# Snake_Game.net
KiCad netlist of a schematic drawn in EAGLE
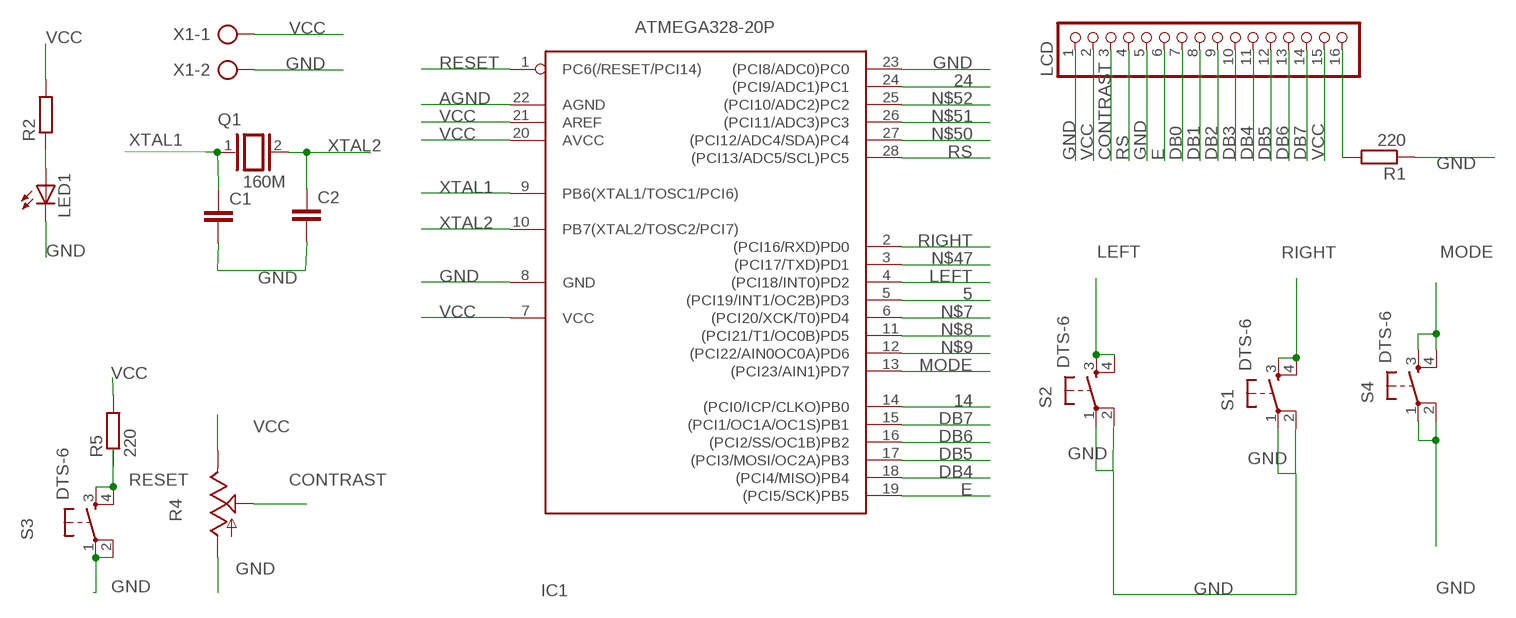
[diagram p0: schematic, sheet 1]

(export (version "E")
  (design (tool "Eeschema 10.0.6"))
  (components
    (comp (ref "C1")
      (value "C2.5/2")
      (footprint "eagle-import:C2.5-2")
      (libsource (lib "eagle-import") (part "C2.5/2"))
    )
    (comp (ref "C2")
      (value "C2.5/2")
      (footprint "eagle-import:C2.5-2")
      (libsource (lib "eagle-import") (part "C2.5/2"))
    )
    (comp (ref "IC1")
      (value "ATMEGA328-20P")
      (footprint "eagle-import:DIL28-3")
      (libsource (lib "eagle-import") (part "ATMEGA328P-20"))
    )
    (comp (ref "LCD")
      (value "PINHD-1X16")
      (footprint "eagle-import:1X16")
      (libsource (lib "eagle-import") (part "PINHD-1X16"))
    )
    (comp (ref "LED1")
      (value "LED_LED3MM")
      (footprint "eagle-import:LED_LED3MM")
      (libsource (lib "eagle-import") (part "LED_LED3MM"))
    )
    (comp (ref "Q1")
      (value "160M")
      (footprint "eagle-import:QS")
      (libsource (lib "eagle-import") (part "XTAL/S"))
    )
    (comp (ref "R1")
      (value "220")
      (footprint "eagle-import:0204_7")
      (libsource (lib "eagle-import") (part "R-EU_0204/7"))
    )
    (comp (ref "R2")
      (value "RCL_R-EU_0204/7")
      (footprint "eagle-import:RCL_0204_7")
      (libsource (lib "eagle-import") (part "RCL_R-EU_0204/7"))
    )
    (comp (ref "R4")
      (value "TRIM_US-B25P")
      (footprint "eagle-import:B25P")
      (libsource (lib "eagle-import") (part "TRIM_US-B25P"))
    )
    (comp (ref "R5")
      (value "220")
      (footprint "eagle-import:0204_7")
      (libsource (lib "eagle-import") (part "R-EU_0204/7"))
    )
    (comp (ref "S1")
      (value "DTS-6")
      (footprint "eagle-import:DTS-6")
      (libsource (lib "eagle-import") (part "DTS-6"))
    )
    (comp (ref "S2")
      (value "DTS-6")
      (footprint "eagle-import:DTS-6")
      (libsource (lib "eagle-import") (part "DTS-6"))
    )
    (comp (ref "S3")
      (value "DTS-6")
      (footprint "eagle-import:DTS-6")
      (libsource (lib "eagle-import") (part "DTS-6"))
    )
    (comp (ref "S4")
      (value "DTS-6")
      (footprint "eagle-import:DTS-6")
      (libsource (lib "eagle-import") (part "DTS-6"))
    )
    (comp (ref "X1")
      (value "AK300/2")
      (footprint "eagle-import:AK300_2")
      (libsource (lib "eagle-import") (part "AK300/2"))
    )
  )
  (nets
    (net (code "1") (name "/5") (class "Default")
      (node (ref "IC1") (pin "5") (pinfunction "(PCI19/INT1/OC2B)PD3_5") (pintype "bidirectional"))
    )
    (net (code "2") (name "/14") (class "Default")
      (node (ref "IC1") (pin "14") (pinfunction "(PCI0/ICP/CLKO)PB0_14") (pintype "bidirectional"))
    )
    (net (code "3") (name "/24") (class "Default")
      (node (ref "IC1") (pin "24") (pinfunction "(PCI9/ADC1)PC1_24") (pintype "bidirectional"))
    )
    (net (code "4") (name "/AGND") (class "Default")
      (node (ref "IC1") (pin "22") (pinfunction "AGND_22") (pintype "bidirectional"))
    )
    (net (code "5") (name "/CONTRAST") (class "Default")
      (node (ref "LCD") (pin "3") (pinfunction "3_3") (pintype "passive"))
      (node (ref "R4") (pin "S") (pinfunction "S_S") (pintype "passive"))
    )
    (net (code "6") (name "/DB0") (class "Default")
      (node (ref "LCD") (pin "7") (pinfunction "7_7") (pintype "passive"))
    )
    (net (code "7") (name "/DB1") (class "Default")
      (node (ref "LCD") (pin "8") (pinfunction "8_8") (pintype "passive"))
    )
    (net (code "8") (name "/DB2") (class "Default")
      (node (ref "LCD") (pin "9") (pinfunction "9_9") (pintype "passive"))
    )
    (net (code "9") (name "/DB3") (class "Default")
      (node (ref "LCD") (pin "10") (pinfunction "10_10") (pintype "passive"))
    )
    (net (code "10") (name "/DB4") (class "Default")
      (node (ref "IC1") (pin "18") (pinfunction "(PCI4/MISO)PB4_18") (pintype "bidirectional"))
      (node (ref "LCD") (pin "11") (pinfunction "11_11") (pintype "passive"))
    )
    (net (code "11") (name "/DB5") (class "Default")
      (node (ref "IC1") (pin "17") (pinfunction "(PCI3/MOSI/OC2A)PB3_17") (pintype "bidirectional"))
      (node (ref "LCD") (pin "12") (pinfunction "12_12") (pintype "passive"))
    )
    (net (code "12") (name "/DB6") (class "Default")
      (node (ref "IC1") (pin "16") (pinfunction "(PCI2/SS/OC1B)PB2_16") (pintype "bidirectional"))
      (node (ref "LCD") (pin "13") (pinfunction "13_13") (pintype "passive"))
    )
    (net (code "13") (name "/DB7") (class "Default")
      (node (ref "IC1") (pin "15") (pinfunction "(PCI1/OC1A/OC1S)PB1_15") (pintype "bidirectional"))
      (node (ref "LCD") (pin "14") (pinfunction "14_14") (pintype "passive"))
    )
    (net (code "14") (name "/E") (class "Default")
      (node (ref "IC1") (pin "19") (pinfunction "(PCI5/SCK)PB5_19") (pintype "bidirectional"))
      (node (ref "LCD") (pin "6") (pinfunction "6_6") (pintype "passive"))
    )
    (net (code "15") (name "/GND") (class "Default")
      (node (ref "C1") (pin "2") (pinfunction "2_2") (pintype "passive"))
      (node (ref "C2") (pin "2") (pinfunction "2_2") (pintype "passive"))
      (node (ref "IC1") (pin "23") (pinfunction "(PCI8/ADC0)PC0_23") (pintype "bidirectional"))
      (node (ref "IC1") (pin "8") (pinfunction "GND_8") (pintype "bidirectional"))
      (node (ref "LCD") (pin "1") (pinfunction "1_1") (pintype "passive"))
      (node (ref "LCD") (pin "5") (pinfunction "5_5") (pintype "passive"))
      (node (ref "LED1") (pin "K") (pinfunction "C_K") (pintype "passive"))
      (node (ref "R1") (pin "1") (pinfunction "1_1") (pintype "passive"))
      (node (ref "R4") (pin "A") (pinfunction "A_A") (pintype "passive"))
      (node (ref "S1") (pin "1") (pinfunction "1_1") (pintype "passive"))
      (node (ref "S1") (pin "2") (pinfunction "2_2") (pintype "passive"))
      (node (ref "S2") (pin "1") (pinfunction "1_1") (pintype "passive"))
      (node (ref "S2") (pin "2") (pinfunction "2_2") (pintype "passive"))
      (node (ref "S3") (pin "1") (pinfunction "1_1") (pintype "passive"))
      (node (ref "S3") (pin "2") (pinfunction "2_2") (pintype "passive"))
      (node (ref "S4") (pin "1") (pinfunction "1_1") (pintype "passive"))
      (node (ref "S4") (pin "2") (pinfunction "2_2") (pintype "passive"))
      (node (ref "X1") (pin "2") (pinfunction "KL_2") (pintype "passive"))
    )
    (net (code "16") (name "/LEFT") (class "Default")
      (node (ref "IC1") (pin "4") (pinfunction "(PCI18/INT0)PD2_4") (pintype "bidirectional"))
      (node (ref "S2") (pin "3") (pinfunction "3_3") (pintype "passive"))
      (node (ref "S2") (pin "4") (pinfunction "4_4") (pintype "passive"))
    )
    (net (code "17") (name "/MODE") (class "Default")
      (node (ref "IC1") (pin "13") (pinfunction "(PCI23/AIN1)PD7_13") (pintype "bidirectional"))
      (node (ref "S4") (pin "3") (pinfunction "3_3") (pintype "passive"))
      (node (ref "S4") (pin "4") (pinfunction "4_4") (pintype "passive"))
    )
    (net (code "18") (name "/N$7") (class "Default")
      (node (ref "IC1") (pin "6") (pinfunction "(PCI20/XCK/T0)PD4_6") (pintype "bidirectional"))
    )
    (net (code "19") (name "/N$8") (class "Default")
      (node (ref "IC1") (pin "11") (pinfunction "(PCI21/T1/OC0B)PD5_11") (pintype "bidirectional"))
    )
    (net (code "20") (name "/N$9") (class "Default")
      (node (ref "IC1") (pin "12") (pinfunction "(PCI22/AIN0OC0A)PD6_12") (pintype "bidirectional"))
    )
    (net (code "21") (name "/N$47") (class "Default")
      (node (ref "IC1") (pin "3") (pinfunction "(PCI17/TXD)PD1_3") (pintype "bidirectional"))
    )
    (net (code "22") (name "/N$50") (class "Default")
      (node (ref "IC1") (pin "27") (pinfunction "(PCI12/ADC4/SDA)PC4_27") (pintype "bidirectional"))
    )
    (net (code "23") (name "/N$51") (class "Default")
      (node (ref "IC1") (pin "26") (pinfunction "(PCI11/ADC3)PC3_26") (pintype "bidirectional"))
    )
    (net (code "24") (name "/N$52") (class "Default")
      (node (ref "IC1") (pin "25") (pinfunction "(PCI10/ADC2)PC2_25") (pintype "bidirectional"))
    )
    (net (code "25") (name "/RESET") (class "Default")
      (node (ref "IC1") (pin "1") (pinfunction "PC6(/RESET/PCI14)_1") (pintype "bidirectional"))
      (node (ref "R5") (pin "1") (pinfunction "1_1") (pintype "passive"))
      (node (ref "S3") (pin "3") (pinfunction "3_3") (pintype "passive"))
      (node (ref "S3") (pin "4") (pinfunction "4_4") (pintype "passive"))
    )
    (net (code "26") (name "/RIGHT") (class "Default")
      (node (ref "IC1") (pin "2") (pinfunction "(PCI16/RXD)PD0_2") (pintype "bidirectional"))
      (node (ref "S1") (pin "3") (pinfunction "3_3") (pintype "passive"))
      (node (ref "S1") (pin "4") (pinfunction "4_4") (pintype "passive"))
    )
    (net (code "27") (name "/RS") (class "Default")
      (node (ref "IC1") (pin "28") (pinfunction "(PCI13/ADC5/SCL)PC5_28") (pintype "bidirectional"))
      (node (ref "LCD") (pin "4") (pinfunction "4_4") (pintype "passive"))
    )
    (net (code "28") (name "/VCC") (class "Default")
      (node (ref "IC1") (pin "20") (pinfunction "AVCC_20") (pintype "bidirectional"))
      (node (ref "IC1") (pin "21") (pinfunction "AREF_21") (pintype "bidirectional"))
      (node (ref "IC1") (pin "7") (pinfunction "VCC_7") (pintype "bidirectional"))
      (node (ref "LCD") (pin "15") (pinfunction "15_15") (pintype "passive"))
      (node (ref "LCD") (pin "2") (pinfunction "2_2") (pintype "passive"))
      (node (ref "R2") (pin "2") (pinfunction "2_2") (pintype "passive"))
      (node (ref "R4") (pin "E") (pinfunction "E_E") (pintype "passive"))
      (node (ref "R5") (pin "2") (pinfunction "2_2") (pintype "passive"))
      (node (ref "X1") (pin "1") (pinfunction "KL_1") (pintype "passive"))
    )
    (net (code "29") (name "/XTAL1") (class "Default")
      (node (ref "C1") (pin "1") (pinfunction "1_1") (pintype "passive"))
      (node (ref "IC1") (pin "9") (pinfunction "PB6(XTAL1/TOSC1/PCI6)_9") (pintype "bidirectional"))
      (node (ref "Q1") (pin "1") (pinfunction "1_1") (pintype "passive"))
    )
    (net (code "30") (name "/XTAL2") (class "Default")
      (node (ref "C2") (pin "1") (pinfunction "1_1") (pintype "passive"))
      (node (ref "IC1") (pin "10") (pinfunction "PB7(XTAL2/TOSC2/PCI7)_10") (pintype "bidirectional"))
      (node (ref "Q1") (pin "2") (pinfunction "2_2") (pintype "passive"))
    )
    (net (code "31") (name "Net-(LCD-Pad16)") (class "Default")
      (node (ref "LCD") (pin "16") (pinfunction "16_16") (pintype "passive"))
      (node (ref "R1") (pin "2") (pinfunction "2_2") (pintype "passive"))
    )
    (net (code "32") (name "Net-(LED1-PadA)") (class "Default")
      (node (ref "LED1") (pin "A") (pinfunction "A_A") (pintype "passive"))
      (node (ref "R2") (pin "1") (pinfunction "1_1") (pintype "passive"))
    )
  )
)
